# fanmon_old.net
KiCad netlist of a schematic drawn in EAGLE
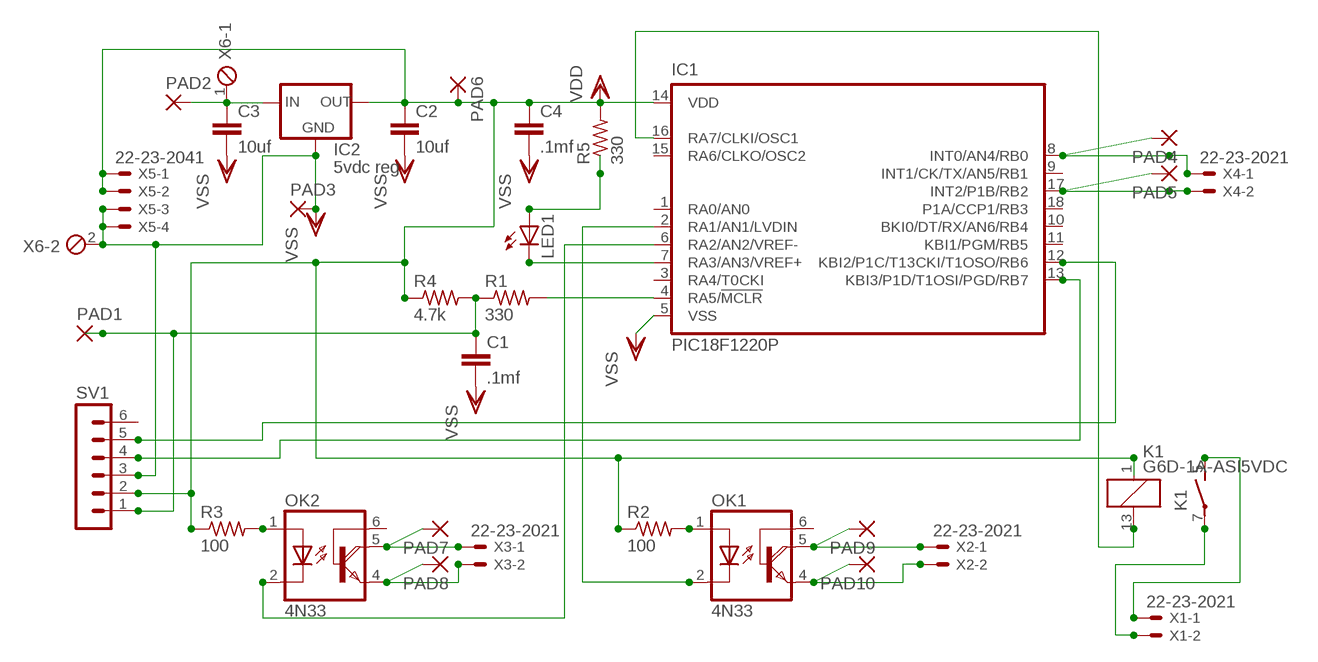
[diagram p0: schematic, sheet 1]

(export (version "E")
  (design (tool "Eeschema 10.0.6"))
  (components
    (comp (ref "C1")
      (value ".1mf")
      (footprint "eagle-import:C5B2.5")
      (libsource (lib "eagle-import") (part "C5/2.5"))
    )
    (comp (ref "C2")
      (value "10uf")
      (footprint "eagle-import:C5B2.5")
      (libsource (lib "eagle-import") (part "C5/2.5"))
    )
    (comp (ref "C3")
      (value "10uf")
      (footprint "eagle-import:C5B2.5")
      (libsource (lib "eagle-import") (part "C5/2.5"))
    )
    (comp (ref "C4")
      (value ".1mf")
      (footprint "eagle-import:C5B2.5")
      (libsource (lib "eagle-import") (part "C5/2.5"))
    )
    (comp (ref "IC1")
      (value "PIC18F1220P")
      (footprint "eagle-import:DIL18")
      (fields (field (name "MF") "MICROCHIP") (field (name "MPN") "PIC18F1220-I/P"))
      (libsource (lib "eagle-import") (part "PIC18F120P2"))
    )
    (comp (ref "IC2")
      (value "5vdc reg")
      (footprint "eagle-import:78XXL")
      (libsource (lib "eagle-import") (part "78XXL"))
    )
    (comp (ref "K1")
      (value "G6D-1A-ASI5VDC")
      (footprint "eagle-import:G6D")
      (libsource (lib "eagle-import") (part "G6D?-1A-ASI5VDC"))
    )
    (comp (ref "LED1")
      (value "LED5MM")
      (footprint "eagle-import:LED5MM")
      (libsource (lib "eagle-import") (part "LED5MM"))
    )
    (comp (ref "OK1")
      (value "4N33")
      (footprint "eagle-import:DIL06")
      (fields (field (name "MF") "VISHAY/TELEFUNKEN"))
      (libsource (lib "eagle-import") (part "4N33"))
    )
    (comp (ref "OK2")
      (value "4N33")
      (footprint "eagle-import:DIL06")
      (fields (field (name "MF") "VISHAY/TELEFUNKEN"))
      (libsource (lib "eagle-import") (part "4N33"))
    )
    (comp (ref "PAD1")
      (value "1,6/0,8")
      (footprint "eagle-import:1,6_0,8")
      (libsource (lib "eagle-import") (part "1,6/0,8"))
    )
    (comp (ref "PAD2")
      (value "1,6/0,8")
      (footprint "eagle-import:1,6_0,8")
      (libsource (lib "eagle-import") (part "1,6/0,8"))
    )
    (comp (ref "PAD3")
      (value "1,6/0,8")
      (footprint "eagle-import:1,6_0,8")
      (libsource (lib "eagle-import") (part "1,6/0,8"))
    )
    (comp (ref "PAD4")
      (value "1,6/0,8")
      (footprint "eagle-import:1,6_0,8")
      (libsource (lib "eagle-import") (part "1,6/0,8"))
    )
    (comp (ref "PAD5")
      (value "1,6/0,8")
      (footprint "eagle-import:1,6_0,8")
      (libsource (lib "eagle-import") (part "1,6/0,8"))
    )
    (comp (ref "PAD6")
      (value "1,6/0,8")
      (footprint "eagle-import:1,6_0,8")
      (libsource (lib "eagle-import") (part "1,6/0,8"))
    )
    (comp (ref "PAD7")
      (value "1,6/0,8")
      (footprint "eagle-import:1,6_0,8")
      (libsource (lib "eagle-import") (part "1,6/0,8"))
    )
    (comp (ref "PAD8")
      (value "1,6/0,8")
      (footprint "eagle-import:1,6_0,8")
      (libsource (lib "eagle-import") (part "1,6/0,8"))
    )
    (comp (ref "PAD9")
      (value "1,6/0,8")
      (footprint "eagle-import:1,6_0,8")
      (libsource (lib "eagle-import") (part "1,6/0,8"))
    )
    (comp (ref "PAD10")
      (value "1,6/0,8")
      (footprint "eagle-import:1,6_0,8")
      (libsource (lib "eagle-import") (part "1,6/0,8"))
    )
    (comp (ref "R1")
      (value "330")
      (footprint "eagle-import:0204V")
      (libsource (lib "eagle-import") (part "R-US_0204/2V"))
    )
    (comp (ref "R2")
      (value "100")
      (footprint "eagle-import:0204V")
      (libsource (lib "eagle-import") (part "R-US_0204/2V"))
    )
    (comp (ref "R3")
      (value "100")
      (footprint "eagle-import:0204V")
      (libsource (lib "eagle-import") (part "R-US_0204/2V"))
    )
    (comp (ref "R4")
      (value "4.7k")
      (footprint "eagle-import:0204V")
      (libsource (lib "eagle-import") (part "R-US_0204/2V"))
    )
    (comp (ref "R5")
      (value "330")
      (footprint "eagle-import:0204V")
      (libsource (lib "eagle-import") (part "R-US_0204/2V"))
    )
    (comp (ref "SV1")
      (value "MA06-1")
      (footprint "eagle-import:MA06-1")
      (libsource (lib "eagle-import") (part "MA06-1"))
    )
    (comp (ref "X1")
      (value "22-23-2021")
      (footprint "eagle-import:22-23-2021")
      (fields (field (name "MF") "MOLEX"))
      (libsource (lib "eagle-import") (part "22-23-2021"))
    )
    (comp (ref "X2")
      (value "22-23-2021")
      (footprint "eagle-import:22-23-2021")
      (fields (field (name "MF") "MOLEX"))
      (libsource (lib "eagle-import") (part "22-23-2021"))
    )
    (comp (ref "X3")
      (value "22-23-2021")
      (footprint "eagle-import:22-23-2021")
      (fields (field (name "MF") "MOLEX"))
      (libsource (lib "eagle-import") (part "22-23-2021"))
    )
    (comp (ref "X4")
      (value "22-23-2021")
      (footprint "eagle-import:22-23-2021")
      (fields (field (name "MF") "MOLEX"))
      (libsource (lib "eagle-import") (part "22-23-2021"))
    )
    (comp (ref "X5")
      (value "22-23-2041")
      (footprint "eagle-import:22-23-2041")
      (fields (field (name "MF") "MOLEX"))
      (libsource (lib "eagle-import") (part "22-23-2041"))
    )
    (comp (ref "X6")
      (value "MPT2")
      (footprint "eagle-import:2POL254")
      (libsource (lib "eagle-import") (part "MPT2"))
    )
  )
  (nets
    (net (code "1") (name "Net-(IC1-INT0{slash}AN4{slash}RB0)") (class "Default")
      (node (ref "IC1") (pin "8") (pinfunction "INT0/AN4/RB0_8") (pintype "bidirectional"))
      (node (ref "PAD4") (pin "1") (pinfunction "P_1") (pintype "passive"))
      (node (ref "X4") (pin "1") (pinfunction "S_1") (pintype "passive"))
    )
    (net (code "2") (name "Net-(IC1-INT2{slash}P1B{slash}RB2)") (class "Default")
      (node (ref "IC1") (pin "17") (pinfunction "INT2/P1B/RB2_17") (pintype "bidirectional"))
      (node (ref "PAD5") (pin "1") (pinfunction "P_1") (pintype "passive"))
      (node (ref "X4") (pin "2") (pinfunction "S_2") (pintype "passive"))
    )
    (net (code "3") (name "Net-(IC1-KBI2{slash}P1C{slash}T13CKI{slash}T1OSO{slash}RB6)") (class "Default")
      (node (ref "IC1") (pin "12") (pinfunction "KBI2/P1C/T13CKI/T1OSO/RB6_12") (pintype "bidirectional"))
      (node (ref "SV1") (pin "5") (pinfunction "5_5") (pintype "passive"))
    )
    (net (code "4") (name "Net-(IC1-KBI3{slash}P1D{slash}T1OSI{slash}PGD{slash}RB7)") (class "Default")
      (node (ref "IC1") (pin "13") (pinfunction "KBI3/P1D/T1OSI/PGD/RB7_13") (pintype "bidirectional"))
      (node (ref "SV1") (pin "4") (pinfunction "4_4") (pintype "passive"))
    )
    (net (code "5") (name "Net-(IC1-RA1{slash}AN1{slash}LVDIN)") (class "Default")
      (node (ref "IC1") (pin "2") (pinfunction "RA1/AN1/LVDIN_2") (pintype "bidirectional"))
      (node (ref "OK1") (pin "2") (pinfunction "C_2") (pintype "passive"))
    )
    (net (code "6") (name "Net-(IC1-RA2{slash}AN2{slash}VREF-)") (class "Default")
      (node (ref "IC1") (pin "6") (pinfunction "RA2/AN2/VREF-_6") (pintype "bidirectional"))
      (node (ref "OK2") (pin "2") (pinfunction "C_2") (pintype "passive"))
    )
    (net (code "7") (name "Net-(IC1-RA3{slash}AN3{slash}VREF+)") (class "Default")
      (node (ref "IC1") (pin "7") (pinfunction "RA3/AN3/VREF+_7") (pintype "bidirectional"))
      (node (ref "LED1") (pin "K") (pinfunction "C_K") (pintype "passive"))
    )
    (net (code "8") (name "Net-(IC1-RA5{slash}~{MCLR})") (class "Default")
      (node (ref "IC1") (pin "4") (pinfunction "RA5/~{MCLR}_4") (pintype "input"))
      (node (ref "R1") (pin "2") (pinfunction "2_2") (pintype "passive"))
    )
    (net (code "9") (name "Net-(IC1-RA7{slash}CLKI{slash}OSC1)") (class "Default")
      (node (ref "IC1") (pin "16") (pinfunction "RA7/CLKI/OSC1_16") (pintype "bidirectional"))
      (node (ref "K1") (pin "13") (pinfunction "2_13") (pintype "passive"))
    )
    (net (code "10") (name "Net-(K1B-P)") (class "Default")
      (node (ref "K1") (pin "7") (pinfunction "P_7") (pintype "passive"))
      (node (ref "X1") (pin "2") (pinfunction "S_2") (pintype "passive"))
    )
    (net (code "11") (name "Net-(K1B-S)") (class "Default")
      (node (ref "K1") (pin "5") (pinfunction "S_5") (pintype "passive"))
      (node (ref "X1") (pin "1") (pinfunction "S_1") (pintype "passive"))
    )
    (net (code "12") (name "Net-(LED1-PadA)") (class "Default")
      (node (ref "LED1") (pin "A") (pinfunction "A_A") (pintype "passive"))
      (node (ref "R5") (pin "1") (pinfunction "1_1") (pintype "passive"))
    )
    (net (code "13") (name "Net-(OK1-A)") (class "Default")
      (node (ref "OK1") (pin "1") (pinfunction "A_1") (pintype "passive"))
      (node (ref "R2") (pin "2") (pinfunction "2_2") (pintype "passive"))
    )
    (net (code "14") (name "Net-(OK1-COL)") (class "Default")
      (node (ref "OK1") (pin "5") (pinfunction "COL_5") (pintype "passive"))
      (node (ref "PAD9") (pin "1") (pinfunction "P_1") (pintype "passive"))
      (node (ref "X2") (pin "1") (pinfunction "S_1") (pintype "passive"))
    )
    (net (code "15") (name "Net-(OK1-E)") (class "Default")
      (node (ref "OK1") (pin "4") (pinfunction "E_4") (pintype "passive"))
      (node (ref "PAD10") (pin "1") (pinfunction "P_1") (pintype "passive"))
      (node (ref "X2") (pin "2") (pinfunction "S_2") (pintype "passive"))
    )
    (net (code "16") (name "Net-(OK2-A)") (class "Default")
      (node (ref "OK2") (pin "1") (pinfunction "A_1") (pintype "passive"))
      (node (ref "R3") (pin "2") (pinfunction "2_2") (pintype "passive"))
    )
    (net (code "17") (name "Net-(OK2-COL)") (class "Default")
      (node (ref "OK2") (pin "5") (pinfunction "COL_5") (pintype "passive"))
      (node (ref "PAD7") (pin "1") (pinfunction "P_1") (pintype "passive"))
      (node (ref "X3") (pin "1") (pinfunction "S_1") (pintype "passive"))
    )
    (net (code "18") (name "Net-(OK2-E)") (class "Default")
      (node (ref "OK2") (pin "4") (pinfunction "E_4") (pintype "passive"))
      (node (ref "PAD8") (pin "1") (pinfunction "P_1") (pintype "passive"))
      (node (ref "X3") (pin "2") (pinfunction "S_2") (pintype "passive"))
    )
    (net (code "19") (name "Net-(PAD1-P)") (class "Default")
      (node (ref "C1") (pin "1") (pinfunction "1_1") (pintype "passive"))
      (node (ref "PAD1") (pin "1") (pinfunction "P_1") (pintype "passive"))
      (node (ref "R1") (pin "1") (pinfunction "1_1") (pintype "passive"))
      (node (ref "R4") (pin "2") (pinfunction "2_2") (pintype "passive"))
      (node (ref "SV1") (pin "1") (pinfunction "1_1") (pintype "passive"))
    )
    (net (code "20") (name "Net-(PAD2-P)") (class "Default")
      (node (ref "C3") (pin "1") (pinfunction "1_1") (pintype "passive"))
      (node (ref "IC2") (pin "IN") (pinfunction "IN_IN") (pintype "input"))
      (node (ref "PAD2") (pin "1") (pinfunction "P_1") (pintype "passive"))
      (node (ref "X6") (pin "1") (pinfunction "1_1") (pintype "passive"))
    )
    (net (code "21") (name "VDD") (class "Default")
      (node (ref "C2") (pin "1") (pinfunction "1_1") (pintype "passive"))
      (node (ref "C4") (pin "1") (pinfunction "1_1") (pintype "passive"))
      (node (ref "IC1") (pin "14") (pinfunction "VDD_14") (pintype "power_in"))
      (node (ref "IC2") (pin "OUT") (pinfunction "OUT_OUT") (pintype "passive"))
      (node (ref "K1") (pin "1") (pinfunction "1_1") (pintype "passive"))
      (node (ref "PAD6") (pin "1") (pinfunction "P_1") (pintype "passive"))
      (node (ref "R2") (pin "1") (pinfunction "1_1") (pintype "passive"))
      (node (ref "R3") (pin "1") (pinfunction "1_1") (pintype "passive"))
      (node (ref "R4") (pin "1") (pinfunction "1_1") (pintype "passive"))
      (node (ref "R5") (pin "2") (pinfunction "2_2") (pintype "passive"))
      (node (ref "SV1") (pin "2") (pinfunction "2_2") (pintype "passive"))
      (node (ref "X5") (pin "1") (pinfunction "S_1") (pintype "passive"))
      (node (ref "X5") (pin "2") (pinfunction "S_2") (pintype "passive"))
    )
    (net (code "22") (name "VSS") (class "Default")
      (node (ref "C1") (pin "2") (pinfunction "2_2") (pintype "passive"))
      (node (ref "C2") (pin "2") (pinfunction "2_2") (pintype "passive"))
      (node (ref "C3") (pin "2") (pinfunction "2_2") (pintype "passive"))
      (node (ref "C4") (pin "2") (pinfunction "2_2") (pintype "passive"))
      (node (ref "IC1") (pin "5") (pinfunction "VSS_5") (pintype "power_in"))
      (node (ref "IC2") (pin "GND") (pinfunction "GND_GND") (pintype "input"))
      (node (ref "PAD3") (pin "1") (pinfunction "P_1") (pintype "passive"))
      (node (ref "SV1") (pin "3") (pinfunction "3_3") (pintype "passive"))
      (node (ref "X5") (pin "3") (pinfunction "S_3") (pintype "passive"))
      (node (ref "X5") (pin "4") (pinfunction "S_4") (pintype "passive"))
      (node (ref "X6") (pin "2") (pinfunction "1_2") (pintype "passive"))
    )
    (net (code "23") (name "unconnected-(IC1-BKI0{slash}DT{slash}RX{slash}AN6{slash}RB4-Pad10)") (class "Default")
      (node (ref "IC1") (pin "10") (pinfunction "BKI0/DT/RX/AN6/RB4_10") (pintype "bidirectional"))
    )
    (net (code "24") (name "unconnected-(IC1-INT1{slash}CK{slash}TX{slash}AN5{slash}RB1-Pad9)") (class "Default")
      (node (ref "IC1") (pin "9") (pinfunction "INT1/CK/TX/AN5/RB1_9") (pintype "bidirectional"))
    )
    (net (code "25") (name "unconnected-(IC1-KBI1{slash}PGM{slash}RB5-Pad11)") (class "Default")
      (node (ref "IC1") (pin "11") (pinfunction "KBI1/PGM/RB5_11") (pintype "bidirectional"))
    )
    (net (code "26") (name "unconnected-(IC1-P1A{slash}CCP1{slash}RB3-Pad18)") (class "Default")
      (node (ref "IC1") (pin "18") (pinfunction "P1A/CCP1/RB3_18") (pintype "bidirectional"))
    )
    (net (code "27") (name "unconnected-(IC1-RA0{slash}AN0-Pad1)") (class "Default")
      (node (ref "IC1") (pin "1") (pinfunction "RA0/AN0_1") (pintype "bidirectional"))
    )
    (net (code "28") (name "unconnected-(IC1-RA4{slash}T0CKI-Pad3)") (class "Default")
      (node (ref "IC1") (pin "3") (pinfunction "RA4/T0CKI_3") (pintype "bidirectional"))
    )
    (net (code "29") (name "unconnected-(IC1-RA6{slash}CLKO{slash}OSC2-Pad15)") (class "Default")
      (node (ref "IC1") (pin "15") (pinfunction "RA6/CLKO/OSC2_15") (pintype "bidirectional"))
    )
    (net (code "30") (name "unconnected-(OK1-B-Pad6)") (class "Default")
      (node (ref "OK1") (pin "6") (pinfunction "B_6") (pintype "passive"))
    )
    (net (code "31") (name "unconnected-(OK2-B-Pad6)") (class "Default")
      (node (ref "OK2") (pin "6") (pinfunction "B_6") (pintype "passive"))
    )
    (net (code "32") (name "unconnected-(SV1-Pad6)") (class "Default")
      (node (ref "SV1") (pin "6") (pinfunction "6_6") (pintype "passive"))
    )
  )
)
